# Jeep_ECU.net
KiCad netlist of a schematic drawn in EAGLE
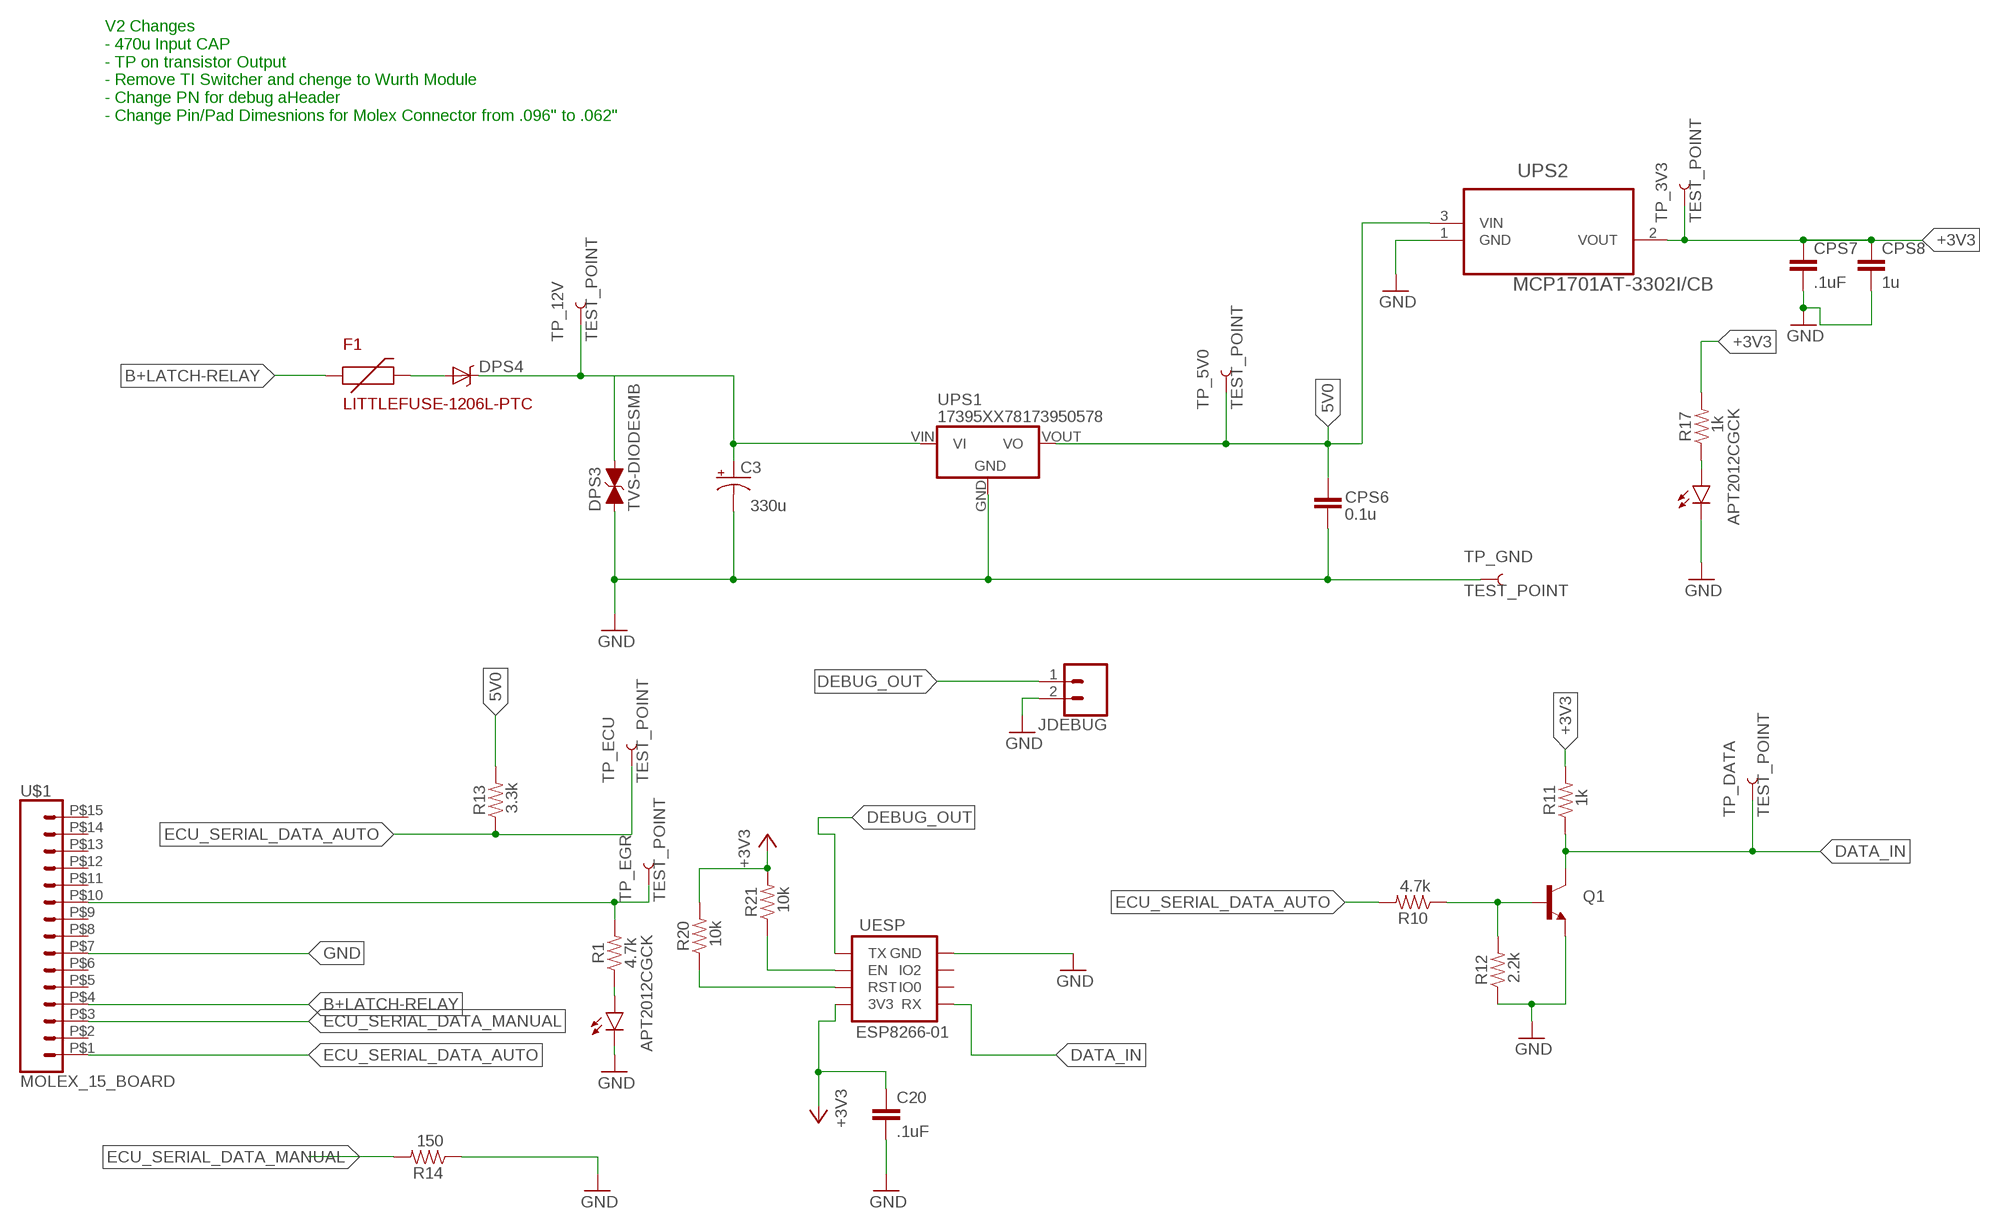
[diagram p0: schematic, sheet 1]

(export (version "E")
  (design (tool "Eeschema 10.0.6"))
  (components
    (comp (ref "C3")
      (value "330u")
      (footprint "eagle-import:8X10MM-ELECTROLYTIC")
      (fields (field (name "MFG") "Nichicon"))
      (libsource (lib "eagle-import") (part "CAP_POLTH1_JE8X10MM-SMD"))
    )
    (comp (ref "C20")
      (value ".1uF")
      (footprint "eagle-import:0603-CAP")
      (fields (field (name "MFG") "Vishay"))
      (libsource (lib "eagle-import") (part "CAP0606-CAP"))
    )
    (comp (ref "CPS6")
      (value "0.1u")
      (footprint "eagle-import:0603-CAP")
      (fields (field (name "MFG") "Vishay"))
      (libsource (lib "eagle-import") (part "CAP0606-CAP"))
    )
    (comp (ref "CPS7")
      (value ".1uF")
      (footprint "eagle-import:0603-CAP")
      (fields (field (name "MFG") "Vishay"))
      (libsource (lib "eagle-import") (part "CAP0606-CAP"))
    )
    (comp (ref "CPS8")
      (value "1u")
      (footprint "eagle-import:0603-CAP")
      (fields (field (name "MFG") "Kemet"))
      (libsource (lib "eagle-import") (part "CAP0606-CAP"))
    )
    (comp (ref "DPS3")
      (value "TVS-DIODESMB")
      (footprint "eagle-import:SMB-DIODE")
      (fields (field (name "MFG") "Littlefuse"))
      (libsource (lib "eagle-import") (part "TVS-DIODESMB"))
    )
    (comp (ref "DPS4")
      (value "SCHOTTKY-DIODESSOD123SOD")
      (footprint "eagle-import:SOD-123F")
      (fields (field (name "MFG") "Fairchild"))
      (libsource (lib "eagle-import") (part "SCHOTTKY-DIODESSODSOD123"))
    )
    (comp (ref "F1")
      (value "LITTLEFUSE-1206L-PTC")
      (footprint "eagle-import:1206")
      (fields (field (name "MFG") "Littlefuse"))
      (libsource (lib "eagle-import") (part "LITTLEFUSE-1206L-PTC"))
    )
    (comp (ref "JDEBUG")
      (value "CONN_02")
      (footprint "eagle-import:1X02")
      (fields (field (name "MFG") "3M"))
      (libsource (lib "eagle-import") (part "CONN_02"))
    )
    (comp (ref "LED_EGR")
      (value "APT2012CGCK")
      (footprint "eagle-import:0805-LED")
      (fields (field (name "MFG") "Kingbright"))
      (libsource (lib "eagle-import") (part "LED0805-PKG"))
    )
    (comp (ref "LED_PWR")
      (value "APT2012CGCK")
      (footprint "eagle-import:0805-LED")
      (fields (field (name "MFG") "Kingbright"))
      (libsource (lib "eagle-import") (part "LED0805-PKG"))
    )
    (comp (ref "Q1")
      (value "NPN-TRANSISTORMMBT3904-SOT23")
      (footprint "eagle-import:SOT23")
      (fields (field (name "MFG") "On Semiconductor"))
      (libsource (lib "eagle-import") (part "NPN-TRANSISTORMMBT3904-SOT23"))
    )
    (comp (ref "R1")
      (value "4.7k")
      (footprint "eagle-import:0603")
      (fields (field (name "MFG") "Panasonic"))
      (libsource (lib "eagle-import") (part "RESISTOR0603"))
    )
    (comp (ref "R10")
      (value "4.7k")
      (footprint "eagle-import:0603")
      (fields (field (name "MFG") "Panasonic"))
      (libsource (lib "eagle-import") (part "RESISTOR0603"))
    )
    (comp (ref "R11")
      (value "1k")
      (footprint "eagle-import:0603")
      (fields (field (name "MFG") "Panasonic"))
      (libsource (lib "eagle-import") (part "RESISTOR0603"))
    )
    (comp (ref "R12")
      (value "2.2k")
      (footprint "eagle-import:0603")
      (fields (field (name "MFG") "Panasonic"))
      (libsource (lib "eagle-import") (part "RESISTOR0603"))
    )
    (comp (ref "R13")
      (value "3.3k")
      (footprint "eagle-import:0603")
      (fields (field (name "MFG") "Panasonic"))
      (libsource (lib "eagle-import") (part "RESISTOR0603"))
    )
    (comp (ref "R14")
      (value "150")
      (footprint "eagle-import:0603")
      (fields (field (name "MFG") "Panasonic"))
      (libsource (lib "eagle-import") (part "RESISTOR0603"))
    )
    (comp (ref "R17")
      (value "1k")
      (footprint "eagle-import:0603")
      (fields (field (name "MFG") "Panasonic"))
      (libsource (lib "eagle-import") (part "RESISTOR0603"))
    )
    (comp (ref "R20")
      (value "10k")
      (footprint "eagle-import:0603")
      (fields (field (name "MFG") "Panasonic"))
      (libsource (lib "eagle-import") (part "RESISTOR0603"))
    )
    (comp (ref "R21")
      (value "10k")
      (footprint "eagle-import:0603")
      (fields (field (name "MFG") "Panasonic"))
      (libsource (lib "eagle-import") (part "RESISTOR0603"))
    )
    (comp (ref "TP_3V3")
      (value "TEST_POINT")
      (footprint "eagle-import:TEST_POINT")
      (fields (field (name "MFG") "Harwin") (field (name "MFG_1") "Harwin") (field (name "PN") "S1751-46"))
      (libsource (lib "eagle-import") (part "TEST_POINT"))
    )
    (comp (ref "TP_5V0")
      (value "TEST_POINT")
      (footprint "eagle-import:TEST_POINT")
      (fields (field (name "MFG") "Harwin") (field (name "MFG_1") "Harwin") (field (name "PN") "S1751-46"))
      (libsource (lib "eagle-import") (part "TEST_POINT"))
    )
    (comp (ref "TP_12V")
      (value "TEST_POINT")
      (footprint "eagle-import:TEST_POINT")
      (fields (field (name "MFG") "Harwin"))
      (libsource (lib "eagle-import") (part "TEST_POINT"))
    )
    (comp (ref "TP_DATA")
      (value "TEST_POINT")
      (footprint "eagle-import:TEST_POINT")
      (fields (field (name "MFG") "Harwin"))
      (libsource (lib "eagle-import") (part "TEST_POINT"))
    )
    (comp (ref "TP_ECU")
      (value "TEST_POINT")
      (footprint "eagle-import:TEST_POINT")
      (fields (field (name "MFG") "Harwin") (field (name "MFG_1") "Harwin") (field (name "PN") "S1751-46"))
      (libsource (lib "eagle-import") (part "TEST_POINT"))
    )
    (comp (ref "TP_EGR")
      (value "TEST_POINT")
      (footprint "eagle-import:TEST_POINT")
      (fields (field (name "MFG") "Harwin"))
      (libsource (lib "eagle-import") (part "TEST_POINT"))
    )
    (comp (ref "TP_GND")
      (value "TEST_POINT")
      (footprint "eagle-import:TEST_POINT")
      (fields (field (name "MFG") "Harwin"))
      (libsource (lib "eagle-import") (part "TEST_POINT"))
    )
    (comp (ref "U$1")
      (value "MOLEX_15_BOARD")
      (footprint "eagle-import:MOLEX_15PIN_BOARD")
      (fields (field (name "MFG") "Molex"))
      (libsource (lib "eagle-import") (part "MOLEX_15_BOARD"))
    )
    (comp (ref "UESP")
      (value "ESP8266-01")
      (footprint "eagle-import:ESP8266-01")
      (fields (field (name "MFG") "3M"))
      (libsource (lib "eagle-import") (part "ESP8266-01"))
    )
    (comp (ref "UPS1")
      (value "17395XX78173950578")
      (footprint "eagle-import:17395XX78")
      (fields (field (name "MFG") "Wurth"))
      (libsource (lib "eagle-import") (part "17395XX78173950578"))
    )
    (comp (ref "UPS2")
      (value "MCP1701AT-3302I/CB")
      (footprint "eagle-import:SOT95P255X145-3N")
      (fields (field (name "MFG") "Microchip"))
      (libsource (lib "eagle-import") (part "MCP1701AT-3302I/CB"))
    )
  )
  (nets
    (net (code "1") (name "+3V3") (class "Default")
      (node (ref "C20") (pin "1") (pinfunction "1_1") (pintype "passive"))
      (node (ref "CPS7") (pin "1") (pinfunction "1_1") (pintype "passive"))
      (node (ref "CPS8") (pin "1") (pinfunction "1_1") (pintype "passive"))
      (node (ref "R11") (pin "2") (pinfunction "2_2") (pintype "passive"))
      (node (ref "R17") (pin "2") (pinfunction "2_2") (pintype "passive"))
      (node (ref "R20") (pin "2") (pinfunction "2_2") (pintype "passive"))
      (node (ref "R21") (pin "2") (pinfunction "2_2") (pintype "passive"))
      (node (ref "TP_3V3") (pin "P$1") (pinfunction "1_P$1") (pintype "bidirectional"))
      (node (ref "UESP") (pin "2") (pinfunction "3V3_2") (pintype "passive"))
      (node (ref "UPS2") (pin "2") (pinfunction "VOUT_2") (pintype "output"))
    )
    (net (code "2") (name "5V0") (class "Default")
      (node (ref "CPS6") (pin "1") (pinfunction "1_1") (pintype "passive"))
      (node (ref "R13") (pin "2") (pinfunction "2_2") (pintype "passive"))
      (node (ref "TP_5V0") (pin "P$1") (pinfunction "1_P$1") (pintype "bidirectional"))
      (node (ref "UPS1") (pin "VOUT") (pinfunction "VO_VOUT") (pintype "passive"))
      (node (ref "UPS2") (pin "3") (pinfunction "VIN_3") (pintype "input"))
    )
    (net (code "3") (name "B+LATCH-RELAY") (class "Default")
      (node (ref "F1") (pin "1") (pinfunction "P$1+_1") (pintype "bidirectional"))
      (node (ref "U$1") (pin "P$4") (pinfunction "4_P$4") (pintype "passive"))
    )
    (net (code "4") (name "DATA_IN") (class "Default")
      (node (ref "Q1") (pin "3") (pinfunction "C_3") (pintype "passive"))
      (node (ref "R11") (pin "1") (pinfunction "1_1") (pintype "passive"))
      (node (ref "TP_DATA") (pin "P$1") (pinfunction "1_P$1") (pintype "bidirectional"))
      (node (ref "UESP") (pin "1") (pinfunction "RX_1") (pintype "passive"))
    )
    (net (code "5") (name "DEBUG_OUT") (class "Default")
      (node (ref "JDEBUG") (pin "1") (pinfunction "1_1") (pintype "passive"))
      (node (ref "UESP") (pin "8") (pinfunction "TX_8") (pintype "passive"))
    )
    (net (code "6") (name "ECU_SERIAL_DATA_AUTO") (class "Default")
      (node (ref "R10") (pin "2") (pinfunction "2_2") (pintype "passive"))
      (node (ref "R13") (pin "1") (pinfunction "1_1") (pintype "passive"))
      (node (ref "TP_ECU") (pin "P$1") (pinfunction "1_P$1") (pintype "bidirectional"))
      (node (ref "U$1") (pin "P$1") (pinfunction "1_P$1") (pintype "passive"))
    )
    (net (code "7") (name "ECU_SERIAL_DATA_MANUAL") (class "Default")
      (node (ref "R14") (pin "2") (pinfunction "2_2") (pintype "passive"))
      (node (ref "U$1") (pin "P$3") (pinfunction "3_P$3") (pintype "passive"))
    )
    (net (code "8") (name "GND") (class "Default")
      (node (ref "C20") (pin "2") (pinfunction "2_2") (pintype "passive"))
      (node (ref "C3") (pin "-") (pinfunction "-_-") (pintype "passive"))
      (node (ref "CPS6") (pin "2") (pinfunction "2_2") (pintype "passive"))
      (node (ref "CPS7") (pin "2") (pinfunction "2_2") (pintype "passive"))
      (node (ref "CPS8") (pin "2") (pinfunction "2_2") (pintype "passive"))
      (node (ref "DPS3") (pin "A") (pinfunction "A_A") (pintype "passive"))
      (node (ref "JDEBUG") (pin "2") (pinfunction "2_2") (pintype "passive"))
      (node (ref "LED_EGR") (pin "C") (pinfunction "C_C") (pintype "passive"))
      (node (ref "LED_PWR") (pin "C") (pinfunction "C_C") (pintype "passive"))
      (node (ref "Q1") (pin "2") (pinfunction "E_2") (pintype "passive"))
      (node (ref "R12") (pin "1") (pinfunction "1_1") (pintype "passive"))
      (node (ref "R14") (pin "1") (pinfunction "1_1") (pintype "passive"))
      (node (ref "TP_GND") (pin "P$1") (pinfunction "1_P$1") (pintype "bidirectional"))
      (node (ref "U$1") (pin "P$7") (pinfunction "7_P$7") (pintype "passive"))
      (node (ref "UESP") (pin "7") (pinfunction "GND_7") (pintype "passive"))
      (node (ref "UPS1") (pin "GND") (pinfunction "GND/ADJ_GND") (pintype "input"))
      (node (ref "UPS2") (pin "1") (pinfunction "GND_1") (pintype "passive"))
    )
    (net (code "9") (name "Net-(F1-P$2-)") (class "Default")
      (node (ref "DPS4") (pin "A") (pinfunction "A_A") (pintype "passive"))
      (node (ref "F1") (pin "2") (pinfunction "P$2-_2") (pintype "bidirectional"))
    )
    (net (code "10") (name "Net-(LED_EGR-PadA)") (class "Default")
      (node (ref "LED_EGR") (pin "A") (pinfunction "A_A") (pintype "passive"))
      (node (ref "R1") (pin "1") (pinfunction "1_1") (pintype "passive"))
    )
    (net (code "11") (name "Net-(LED_PWR-PadA)") (class "Default")
      (node (ref "LED_PWR") (pin "A") (pinfunction "A_A") (pintype "passive"))
      (node (ref "R17") (pin "1") (pinfunction "1_1") (pintype "passive"))
    )
    (net (code "12") (name "Net-(Q1-B)") (class "Default")
      (node (ref "Q1") (pin "1") (pinfunction "B_1") (pintype "passive"))
      (node (ref "R10") (pin "1") (pinfunction "1_1") (pintype "passive"))
      (node (ref "R12") (pin "2") (pinfunction "2_2") (pintype "passive"))
    )
    (net (code "13") (name "Net-(TP_12V-1)") (class "Default")
      (node (ref "C3") (pin "+") (pinfunction "+_+") (pintype "passive"))
      (node (ref "DPS3") (pin "C") (pinfunction "C_C") (pintype "passive"))
      (node (ref "DPS4") (pin "C") (pinfunction "C_C") (pintype "passive"))
      (node (ref "TP_12V") (pin "P$1") (pinfunction "1_P$1") (pintype "bidirectional"))
      (node (ref "UPS1") (pin "VIN") (pinfunction "VI_VIN") (pintype "input"))
    )
    (net (code "14") (name "Net-(TP_EGR-1)") (class "Default")
      (node (ref "R1") (pin "2") (pinfunction "2_2") (pintype "passive"))
      (node (ref "TP_EGR") (pin "P$1") (pinfunction "1_P$1") (pintype "bidirectional"))
      (node (ref "U$1") (pin "P$10") (pinfunction "10_P$10") (pintype "passive"))
    )
    (net (code "15") (name "Net-(UESP-EN)") (class "Default")
      (node (ref "R21") (pin "1") (pinfunction "1_1") (pintype "passive"))
      (node (ref "UESP") (pin "6") (pinfunction "EN_6") (pintype "passive"))
    )
    (net (code "16") (name "Net-(UESP-RST)") (class "Default")
      (node (ref "R20") (pin "1") (pinfunction "1_1") (pintype "passive"))
      (node (ref "UESP") (pin "4") (pinfunction "RST_4") (pintype "passive"))
    )
    (net (code "17") (name "unconnected-(U$1-2-PadP$2)") (class "Default")
      (node (ref "U$1") (pin "P$2") (pinfunction "2_P$2") (pintype "passive"))
    )
    (net (code "18") (name "unconnected-(U$1-5-PadP$5)") (class "Default")
      (node (ref "U$1") (pin "P$5") (pinfunction "5_P$5") (pintype "passive"))
    )
    (net (code "19") (name "unconnected-(U$1-6-PadP$6)") (class "Default")
      (node (ref "U$1") (pin "P$6") (pinfunction "6_P$6") (pintype "passive"))
    )
    (net (code "20") (name "unconnected-(U$1-8-PadP$8)") (class "Default")
      (node (ref "U$1") (pin "P$8") (pinfunction "8_P$8") (pintype "passive"))
    )
    (net (code "21") (name "unconnected-(U$1-9-PadP$9)") (class "Default")
      (node (ref "U$1") (pin "P$9") (pinfunction "9_P$9") (pintype "passive"))
    )
    (net (code "22") (name "unconnected-(U$1-11-PadP$11)") (class "Default")
      (node (ref "U$1") (pin "P$11") (pinfunction "11_P$11") (pintype "passive"))
    )
    (net (code "23") (name "unconnected-(U$1-12-PadP$12)") (class "Default")
      (node (ref "U$1") (pin "P$12") (pinfunction "12_P$12") (pintype "passive"))
    )
    (net (code "24") (name "unconnected-(U$1-13-PadP$13)") (class "Default")
      (node (ref "U$1") (pin "P$13") (pinfunction "13_P$13") (pintype "passive"))
    )
    (net (code "25") (name "unconnected-(U$1-14-PadP$14)") (class "Default")
      (node (ref "U$1") (pin "P$14") (pinfunction "14_P$14") (pintype "passive"))
    )
    (net (code "26") (name "unconnected-(U$1-15-PadP$15)") (class "Default")
      (node (ref "U$1") (pin "P$15") (pinfunction "15_P$15") (pintype "passive"))
    )
    (net (code "27") (name "unconnected-(UESP-IO0-Pad3)") (class "Default")
      (node (ref "UESP") (pin "3") (pinfunction "IO0_3") (pintype "passive"))
    )
    (net (code "28") (name "unconnected-(UESP-IO2-Pad5)") (class "Default")
      (node (ref "UESP") (pin "5") (pinfunction "IO2_5") (pintype "passive"))
    )
  )
)
